# RN2483A.net
KiCad netlist of a schematic drawn in Altium Designer
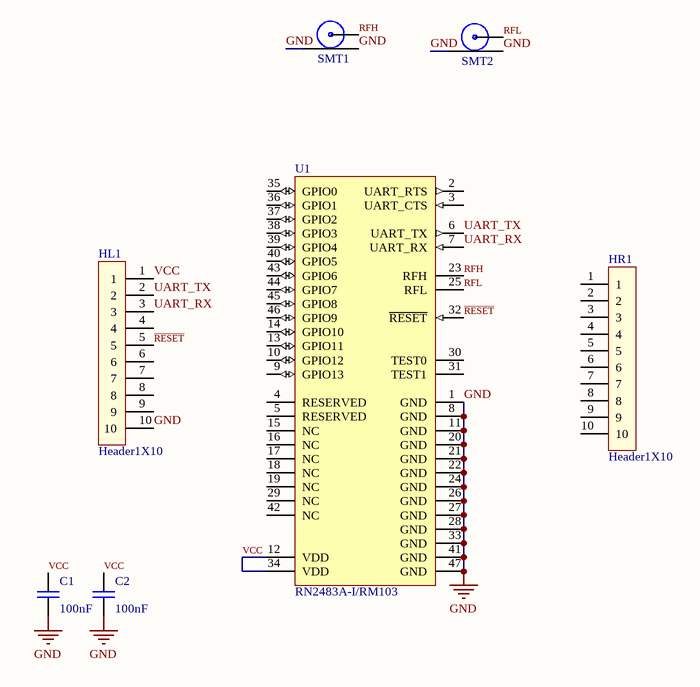
[diagram p0: RN2483A.SchDoc]

(export (version "E")
  (design (tool "Eeschema 10.0.6"))
  (components
    (comp (ref "C1")
      (value "100nF")
      (footprint "C0603")
      (description "C0603")
      (fields (field (name "Comment") "02016D104KAT2A"))
      (libsource (lib "Passive components") (part "02016D104KAT2A"))
    )
    (comp (ref "C2")
      (value "100nF")
      (footprint "C0603")
      (description "C0603")
      (fields (field (name "Comment") "02016D104KAT2A"))
      (libsource (lib "Passive components") (part "02016D104KAT2A"))
    )
    (comp (ref "HL1")
      (value "Header1X10")
      (footprint "Header1X10")
      (libsource (lib "Header1X10") (part "Header1X10"))
    )
    (comp (ref "HR1")
      (value "Header1X10")
      (footprint "Header1X10")
      (libsource (lib "") (part "Header1X10_1"))
    )
    (comp (ref "SMT1")
      (value "U.FL-R-SMT")
      (footprint "*U.FL-R-SMT_U.FL-R-SMT(Primary)")
      (fields (field (name "MF") "Hirose Electric"))
      (libsource (lib "U.FL-R-SMT") (part "U.FL-R-SMT"))
    )
    (comp (ref "SMT2")
      (value "U.FL-R-SMT")
      (footprint "*U.FL-R-SMT_U.FL-R-SMT(Primary)")
      (fields (field (name "MF") "Hirose Electric"))
      (libsource (lib "U.FL-R-SMT") (part "U.FL-R-SMT"))
    )
    (comp (ref "U1")
      (value "RN2483A-I/RM103")
      (footprint "MCHP-MODULE-47_V")
      (fields (field (name "MANUFACTURER") "Microchip"))
      (libsource (lib "Altium Content Vault") (part "MCHP-RN2483-MODULE-47"))
    )
  )
  (nets
    (net (code "1") (name "/RFH") (class "Default")
      (node (ref "SMT1") (pin "P$1") (pinfunction "P$1_P$1") (pintype "passive"))
      (node (ref "U1") (pin "23") (pinfunction "RFH_23") (pintype "passive"))
    )
    (net (code "2") (name "/RFL") (class "Default")
      (node (ref "SMT2") (pin "P$1") (pinfunction "P$1_P$1") (pintype "passive"))
      (node (ref "U1") (pin "25") (pinfunction "RFL_25") (pintype "passive"))
    )
    (net (code "3") (name "/UART_RX") (class "Default")
      (node (ref "HL1") (pin "3") (pinfunction "3_3") (pintype "passive"))
      (node (ref "U1") (pin "7") (pinfunction "UART_RX_7") (pintype "input"))
    )
    (net (code "4") (name "/UART_TX") (class "Default")
      (node (ref "HL1") (pin "2") (pinfunction "2_2") (pintype "passive"))
      (node (ref "U1") (pin "6") (pinfunction "UART_TX_6") (pintype "output"))
    )
    (net (code "5") (name "/VCC") (class "Default")
      (node (ref "C1") (pin "2") (pinfunction "2_2") (pintype "passive"))
      (node (ref "C2") (pin "2") (pinfunction "2_2") (pintype "passive"))
      (node (ref "HL1") (pin "1") (pinfunction "1_1") (pintype "passive"))
      (node (ref "U1") (pin "12") (pinfunction "VDD_12") (pintype "power_in"))
      (node (ref "U1") (pin "34") (pinfunction "VDD_34") (pintype "power_in"))
    )
    (net (code "6") (name "/~{RESET}") (class "Default")
      (node (ref "HL1") (pin "5") (pinfunction "5_5") (pintype "passive"))
      (node (ref "U1") (pin "32") (pinfunction "~{RESET}_32") (pintype "input"))
    )
    (net (code "7") (name "GND") (class "Default")
      (node (ref "C1") (pin "1") (pinfunction "1_1") (pintype "passive"))
      (node (ref "C2") (pin "1") (pinfunction "1_1") (pintype "passive"))
      (node (ref "HL1") (pin "10") (pinfunction "10_10") (pintype "passive"))
      (node (ref "SMT1") (pin "P$2") (pinfunction "P$2_P$2") (pintype "power_in"))
      (node (ref "SMT1") (pin "P$3") (pinfunction "P$3_P$3") (pintype "power_in"))
      (node (ref "SMT2") (pin "P$2") (pinfunction "P$2_P$2") (pintype "power_in"))
      (node (ref "SMT2") (pin "P$3") (pinfunction "P$3_P$3") (pintype "power_in"))
      (node (ref "U1") (pin "1") (pinfunction "GND_1") (pintype "power_in"))
      (node (ref "U1") (pin "11") (pinfunction "GND_11") (pintype "power_in"))
      (node (ref "U1") (pin "20") (pinfunction "GND_20") (pintype "power_in"))
      (node (ref "U1") (pin "21") (pinfunction "GND_21") (pintype "power_in"))
      (node (ref "U1") (pin "22") (pinfunction "GND_22") (pintype "power_in"))
      (node (ref "U1") (pin "24") (pinfunction "GND_24") (pintype "power_in"))
      (node (ref "U1") (pin "26") (pinfunction "GND_26") (pintype "power_in"))
      (node (ref "U1") (pin "27") (pinfunction "GND_27") (pintype "power_in"))
      (node (ref "U1") (pin "28") (pinfunction "GND_28") (pintype "power_in"))
      (node (ref "U1") (pin "33") (pinfunction "GND_33") (pintype "power_in"))
      (node (ref "U1") (pin "41") (pinfunction "GND_41") (pintype "power_in"))
      (node (ref "U1") (pin "47") (pinfunction "GND_47") (pintype "power_in"))
      (node (ref "U1") (pin "8") (pinfunction "GND_8") (pintype "power_in"))
    )
    (net (code "8") (name "unconnected-(HL1-Pad4)") (class "Default")
      (node (ref "HL1") (pin "4") (pinfunction "4_4") (pintype "passive"))
    )
    (net (code "9") (name "unconnected-(HL1-Pad6)") (class "Default")
      (node (ref "HL1") (pin "6") (pinfunction "6_6") (pintype "passive"))
    )
    (net (code "10") (name "unconnected-(HL1-Pad7)") (class "Default")
      (node (ref "HL1") (pin "7") (pinfunction "7_7") (pintype "passive"))
    )
    (net (code "11") (name "unconnected-(HL1-Pad8)") (class "Default")
      (node (ref "HL1") (pin "8") (pinfunction "8_8") (pintype "passive"))
    )
    (net (code "12") (name "unconnected-(HL1-Pad9)") (class "Default")
      (node (ref "HL1") (pin "9") (pinfunction "9_9") (pintype "passive"))
    )
    (net (code "13") (name "unconnected-(HR1-Pad1)") (class "Default")
      (node (ref "HR1") (pin "1") (pinfunction "1_1") (pintype "passive"))
    )
    (net (code "14") (name "unconnected-(HR1-Pad2)") (class "Default")
      (node (ref "HR1") (pin "2") (pinfunction "2_2") (pintype "passive"))
    )
    (net (code "15") (name "unconnected-(HR1-Pad3)") (class "Default")
      (node (ref "HR1") (pin "3") (pinfunction "3_3") (pintype "passive"))
    )
    (net (code "16") (name "unconnected-(HR1-Pad4)") (class "Default")
      (node (ref "HR1") (pin "4") (pinfunction "4_4") (pintype "passive"))
    )
    (net (code "17") (name "unconnected-(HR1-Pad5)") (class "Default")
      (node (ref "HR1") (pin "5") (pinfunction "5_5") (pintype "passive"))
    )
    (net (code "18") (name "unconnected-(HR1-Pad6)") (class "Default")
      (node (ref "HR1") (pin "6") (pinfunction "6_6") (pintype "passive"))
    )
    (net (code "19") (name "unconnected-(HR1-Pad7)") (class "Default")
      (node (ref "HR1") (pin "7") (pinfunction "7_7") (pintype "passive"))
    )
    (net (code "20") (name "unconnected-(HR1-Pad8)") (class "Default")
      (node (ref "HR1") (pin "8") (pinfunction "8_8") (pintype "passive"))
    )
    (net (code "21") (name "unconnected-(HR1-Pad9)") (class "Default")
      (node (ref "HR1") (pin "9") (pinfunction "9_9") (pintype "passive"))
    )
    (net (code "22") (name "unconnected-(HR1-Pad10)") (class "Default")
      (node (ref "HR1") (pin "10") (pinfunction "10_10") (pintype "passive"))
    )
    (net (code "23") (name "unconnected-(U1-GPIO0-Pad35)") (class "Default")
      (node (ref "U1") (pin "35") (pinfunction "GPIO0_35") (pintype "bidirectional"))
    )
    (net (code "24") (name "unconnected-(U1-GPIO1-Pad36)") (class "Default")
      (node (ref "U1") (pin "36") (pinfunction "GPIO1_36") (pintype "bidirectional"))
    )
    (net (code "25") (name "unconnected-(U1-GPIO2-Pad37)") (class "Default")
      (node (ref "U1") (pin "37") (pinfunction "GPIO2_37") (pintype "bidirectional"))
    )
    (net (code "26") (name "unconnected-(U1-GPIO3-Pad38)") (class "Default")
      (node (ref "U1") (pin "38") (pinfunction "GPIO3_38") (pintype "bidirectional"))
    )
    (net (code "27") (name "unconnected-(U1-GPIO4-Pad39)") (class "Default")
      (node (ref "U1") (pin "39") (pinfunction "GPIO4_39") (pintype "bidirectional"))
    )
    (net (code "28") (name "unconnected-(U1-GPIO5-Pad40)") (class "Default")
      (node (ref "U1") (pin "40") (pinfunction "GPIO5_40") (pintype "bidirectional"))
    )
    (net (code "29") (name "unconnected-(U1-GPIO6-Pad43)") (class "Default")
      (node (ref "U1") (pin "43") (pinfunction "GPIO6_43") (pintype "bidirectional"))
    )
    (net (code "30") (name "unconnected-(U1-GPIO7-Pad44)") (class "Default")
      (node (ref "U1") (pin "44") (pinfunction "GPIO7_44") (pintype "bidirectional"))
    )
    (net (code "31") (name "unconnected-(U1-GPIO8-Pad45)") (class "Default")
      (node (ref "U1") (pin "45") (pinfunction "GPIO8_45") (pintype "bidirectional"))
    )
    (net (code "32") (name "unconnected-(U1-GPIO9-Pad46)") (class "Default")
      (node (ref "U1") (pin "46") (pinfunction "GPIO9_46") (pintype "bidirectional"))
    )
    (net (code "33") (name "unconnected-(U1-GPIO10-Pad14)") (class "Default")
      (node (ref "U1") (pin "14") (pinfunction "GPIO10_14") (pintype "bidirectional"))
    )
    (net (code "34") (name "unconnected-(U1-GPIO11-Pad13)") (class "Default")
      (node (ref "U1") (pin "13") (pinfunction "GPIO11_13") (pintype "bidirectional"))
    )
    (net (code "35") (name "unconnected-(U1-GPIO12-Pad10)") (class "Default")
      (node (ref "U1") (pin "10") (pinfunction "GPIO12_10") (pintype "bidirectional"))
    )
    (net (code "36") (name "unconnected-(U1-GPIO13-Pad9)") (class "Default")
      (node (ref "U1") (pin "9") (pinfunction "GPIO13_9") (pintype "bidirectional"))
    )
    (net (code "37") (name "unconnected-(U1-NC-Pad15)") (class "Default")
      (node (ref "U1") (pin "15") (pinfunction "NC_15") (pintype "passive"))
    )
    (net (code "38") (name "unconnected-(U1-NC-Pad16)") (class "Default")
      (node (ref "U1") (pin "16") (pinfunction "NC_16") (pintype "passive"))
    )
    (net (code "39") (name "unconnected-(U1-NC-Pad17)") (class "Default")
      (node (ref "U1") (pin "17") (pinfunction "NC_17") (pintype "passive"))
    )
    (net (code "40") (name "unconnected-(U1-NC-Pad18)") (class "Default")
      (node (ref "U1") (pin "18") (pinfunction "NC_18") (pintype "passive"))
    )
    (net (code "41") (name "unconnected-(U1-NC-Pad19)") (class "Default")
      (node (ref "U1") (pin "19") (pinfunction "NC_19") (pintype "passive"))
    )
    (net (code "42") (name "unconnected-(U1-NC-Pad29)") (class "Default")
      (node (ref "U1") (pin "29") (pinfunction "NC_29") (pintype "passive"))
    )
    (net (code "43") (name "unconnected-(U1-NC-Pad42)") (class "Default")
      (node (ref "U1") (pin "42") (pinfunction "NC_42") (pintype "passive"))
    )
    (net (code "44") (name "unconnected-(U1-RESERVED-Pad4)") (class "Default")
      (node (ref "U1") (pin "4") (pinfunction "RESERVED_4") (pintype "passive"))
    )
    (net (code "45") (name "unconnected-(U1-RESERVED-Pad5)") (class "Default")
      (node (ref "U1") (pin "5") (pinfunction "RESERVED_5") (pintype "passive"))
    )
    (net (code "46") (name "unconnected-(U1-TEST0-Pad30)") (class "Default")
      (node (ref "U1") (pin "30") (pinfunction "TEST0_30") (pintype "passive"))
    )
    (net (code "47") (name "unconnected-(U1-TEST1-Pad31)") (class "Default")
      (node (ref "U1") (pin "31") (pinfunction "TEST1_31") (pintype "passive"))
    )
    (net (code "48") (name "unconnected-(U1-UART_CTS-Pad3)") (class "Default")
      (node (ref "U1") (pin "3") (pinfunction "UART_CTS_3") (pintype "input"))
    )
    (net (code "49") (name "unconnected-(U1-UART_RTS-Pad2)") (class "Default")
      (node (ref "U1") (pin "2") (pinfunction "UART_RTS_2") (pintype "output"))
    )
  )
)
